# DVD.net
KiCad netlist of a schematic drawn in Altium Designer
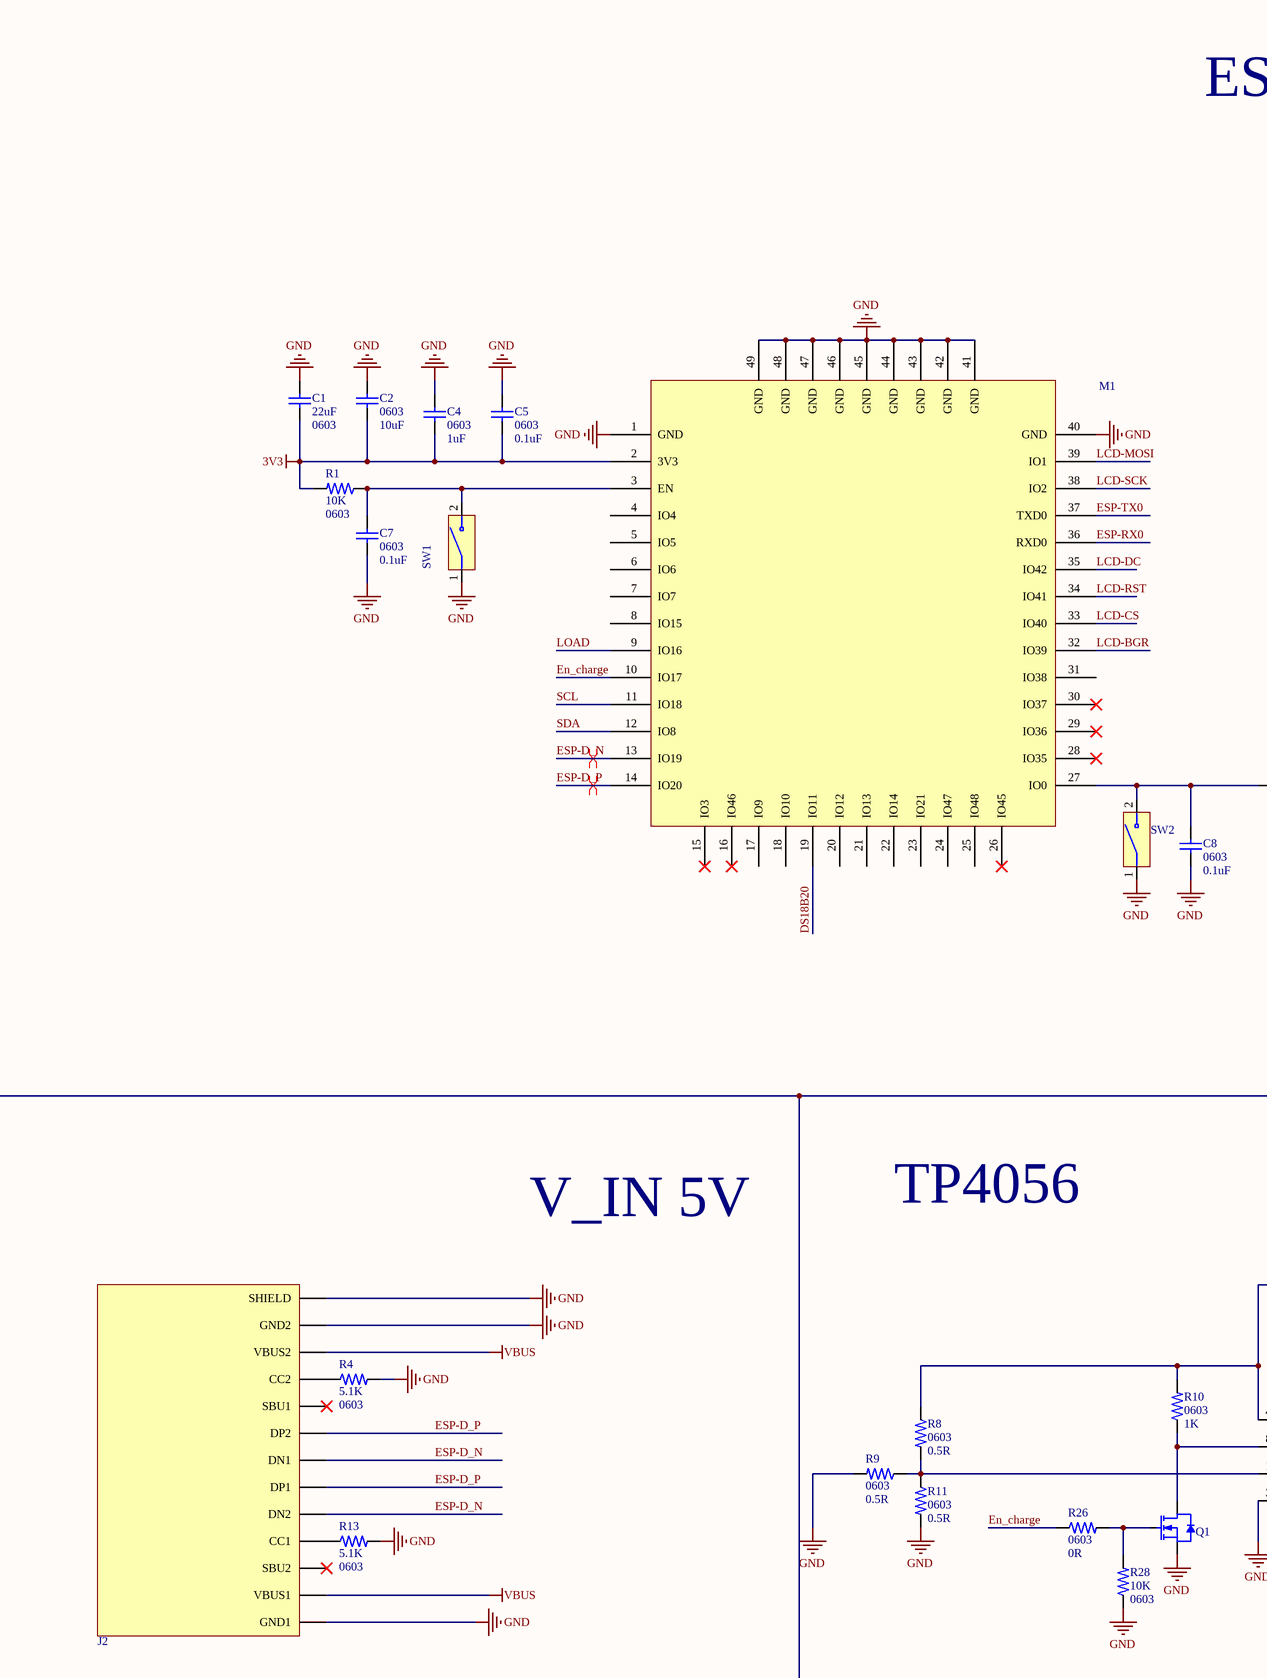
[diagram p0: DVD.SchDoc, top left]
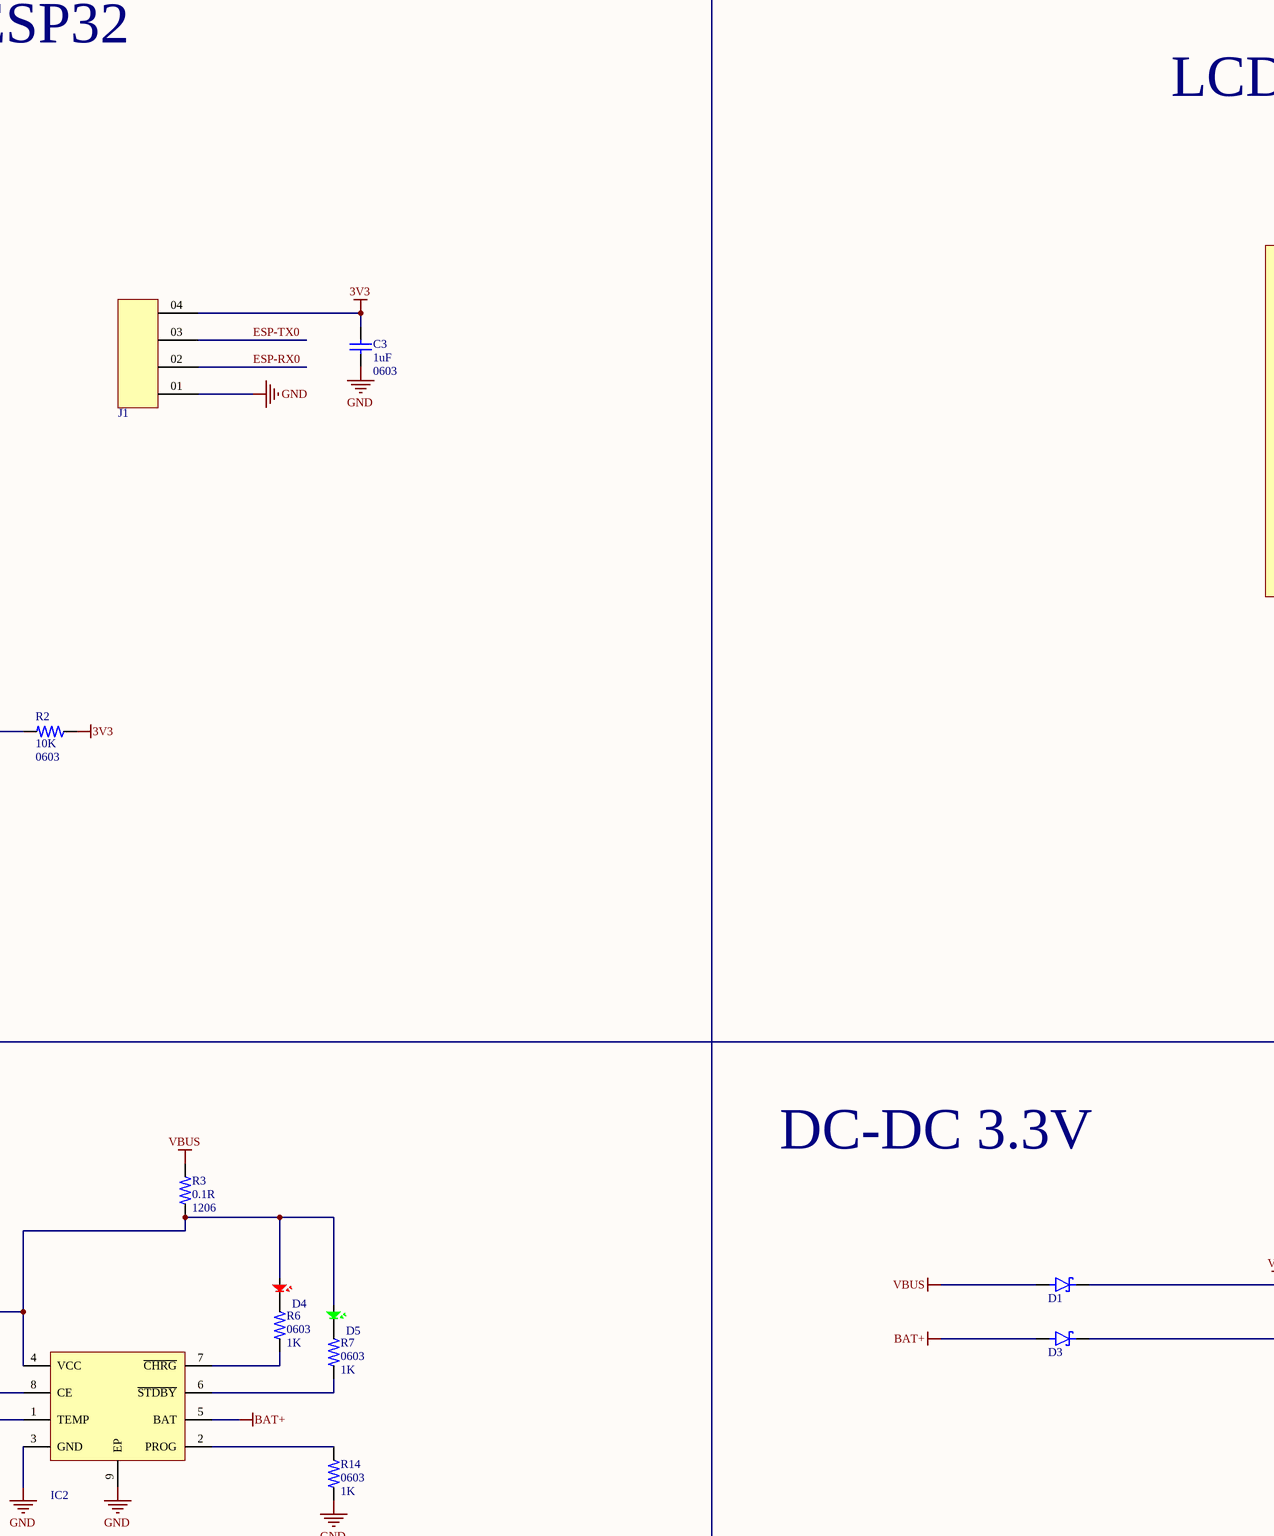
[diagram p1: DVD.SchDoc, top middle]
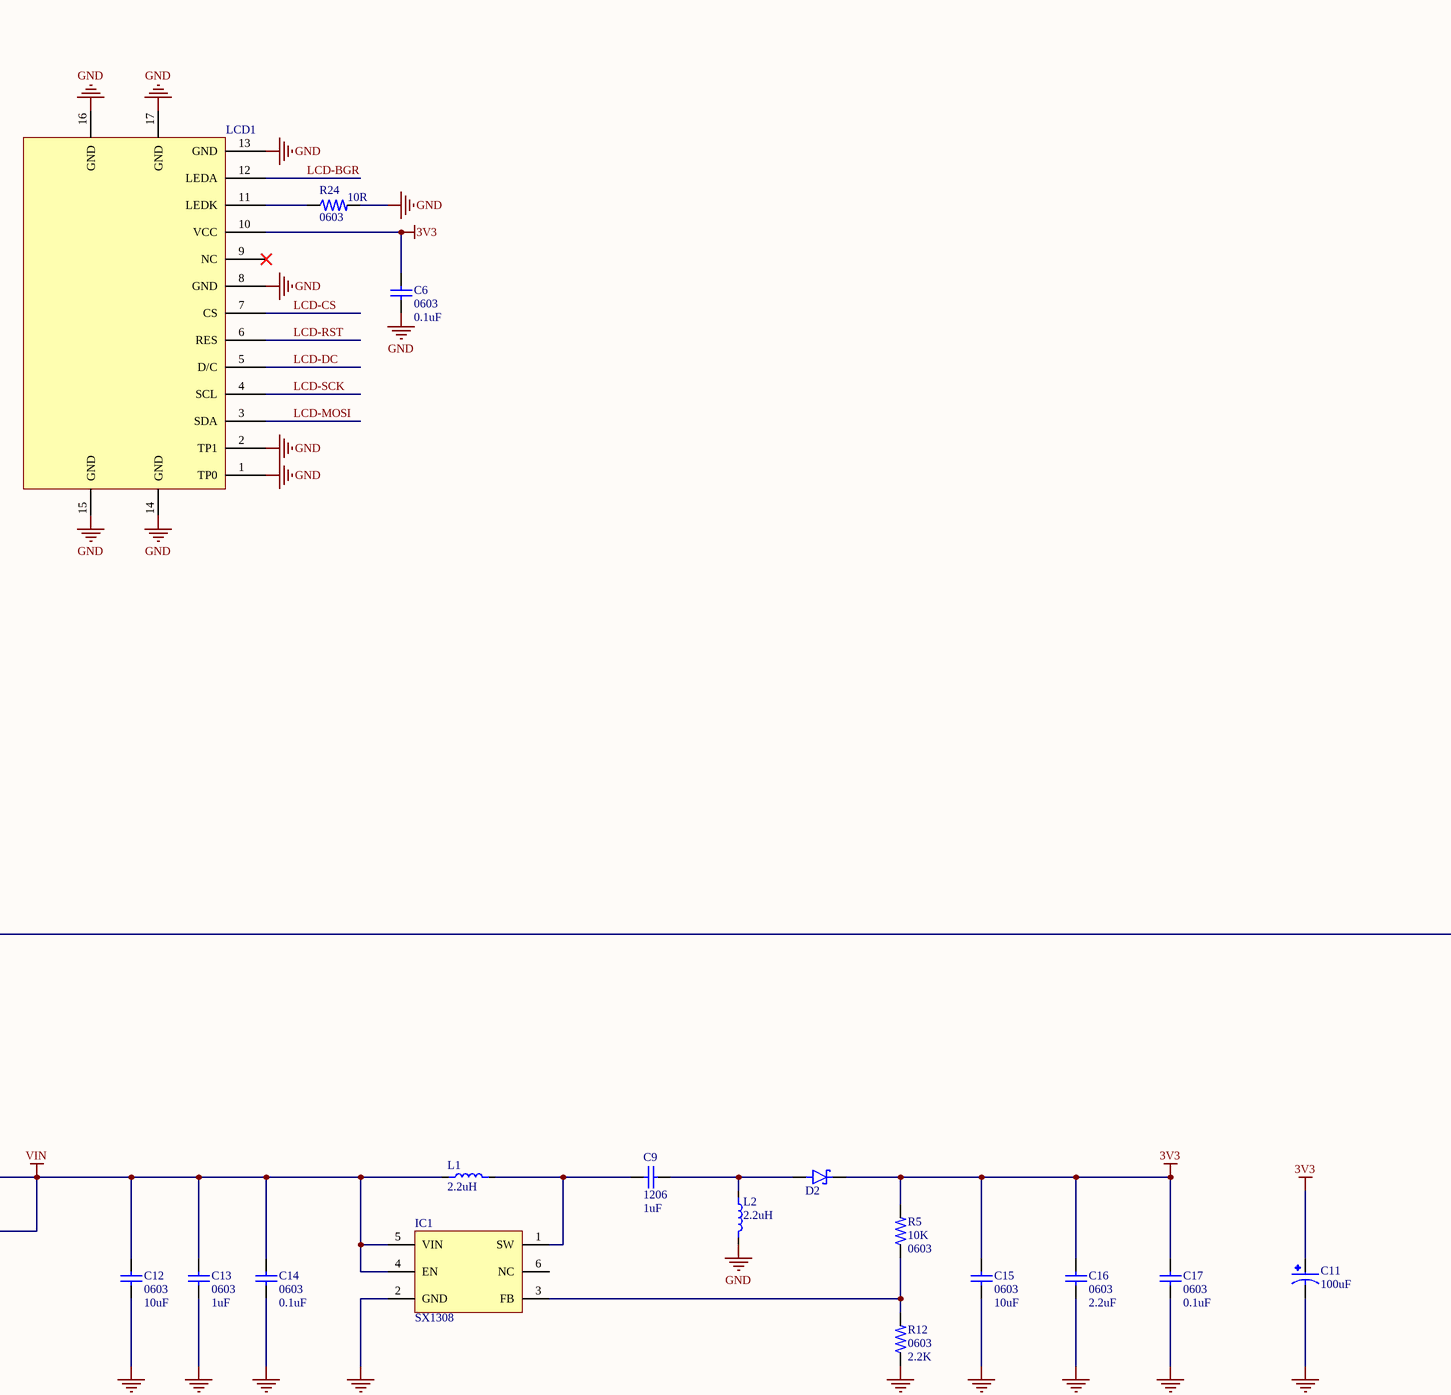
[diagram p2: DVD.SchDoc, top right]
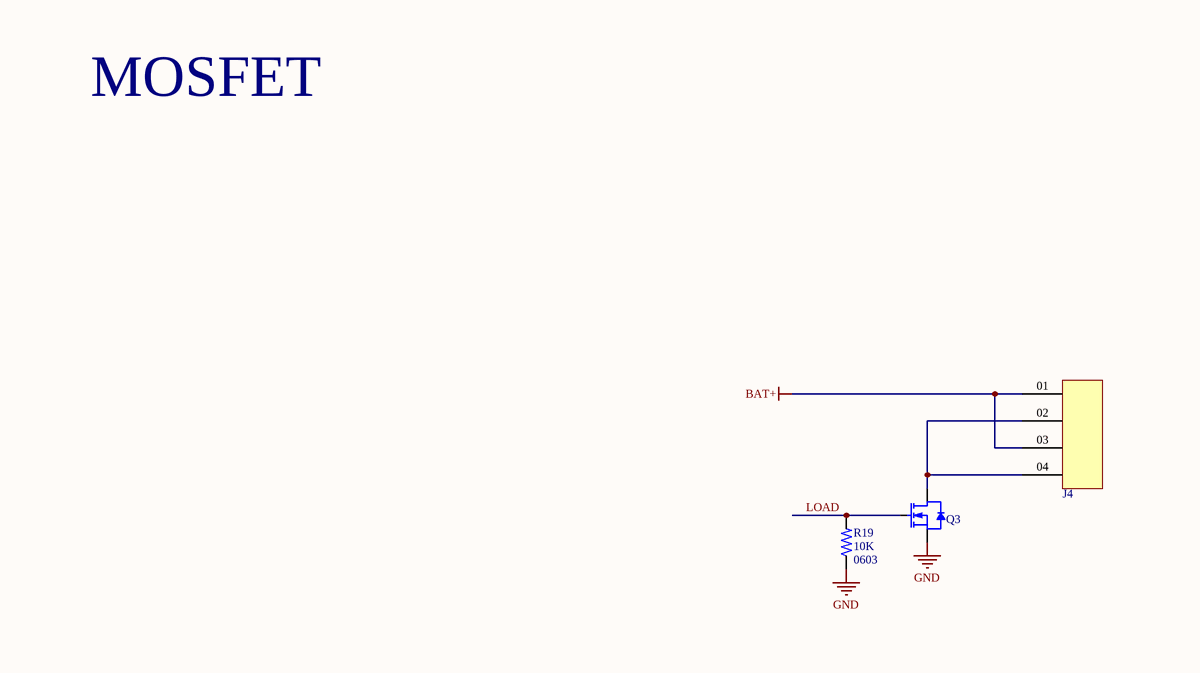
[diagram p3: DVD.SchDoc, bottom left]
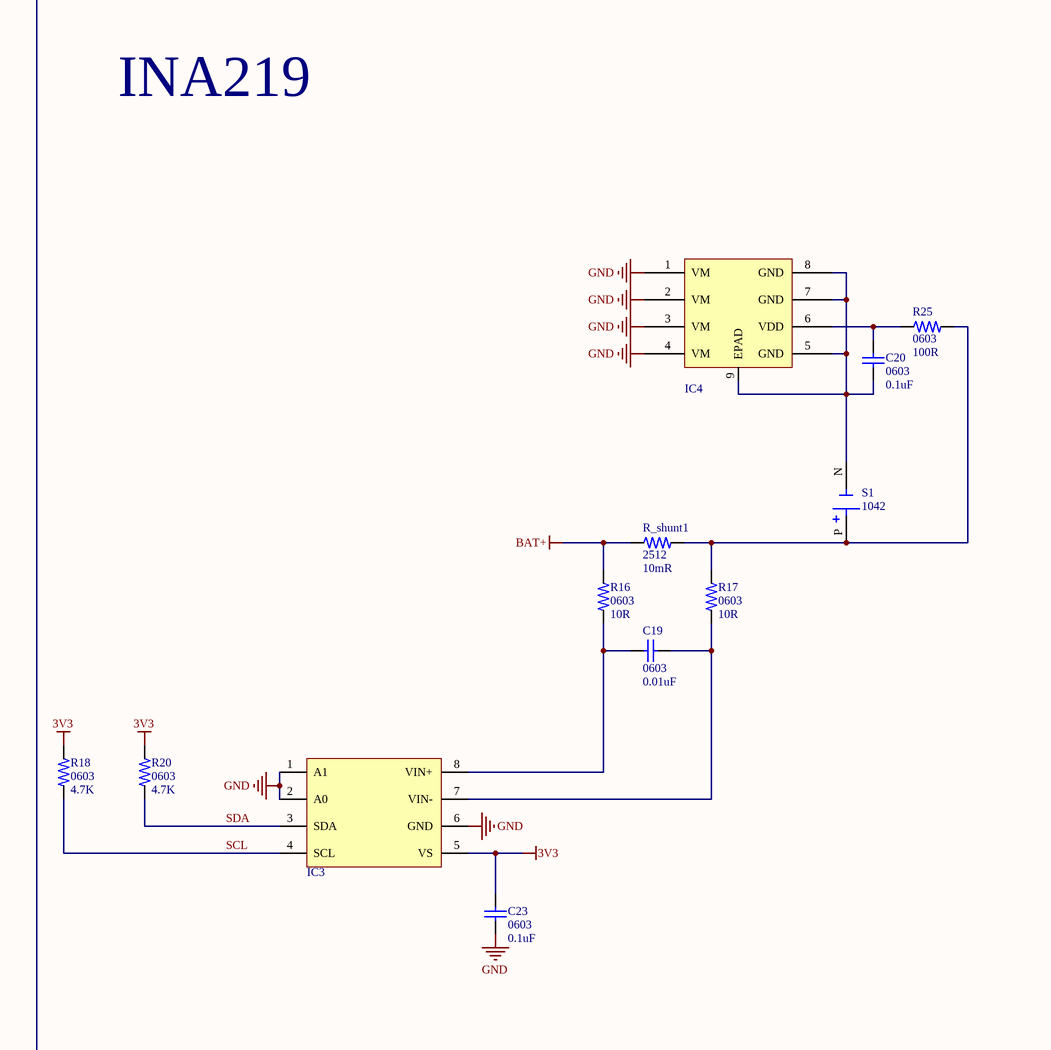
[diagram p4: DVD.SchDoc, bottom middle]
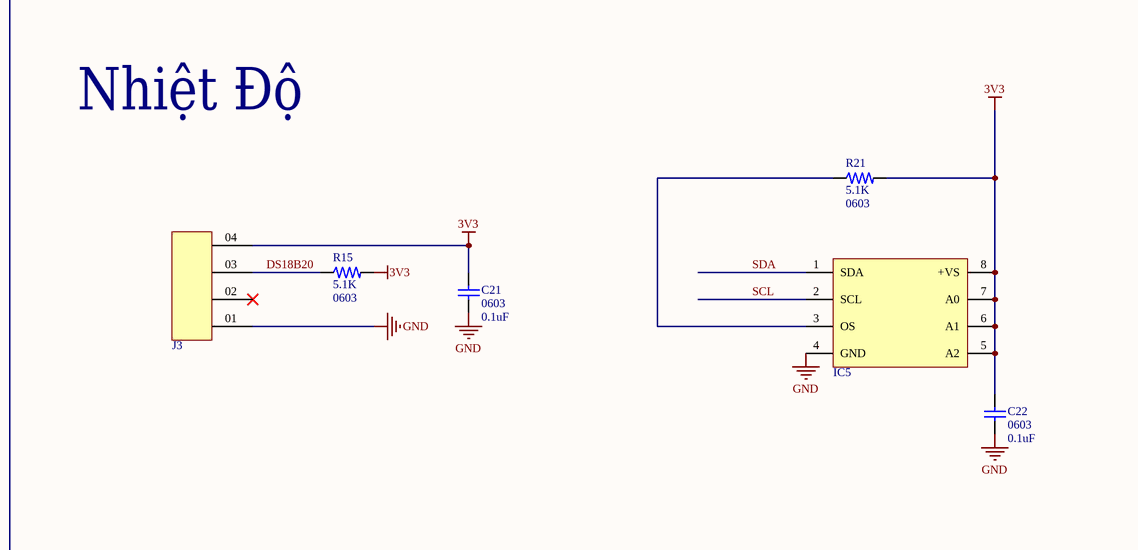
[diagram p5: DVD.SchDoc, bottom right]

(export (version "E")
  (design (tool "Eeschema 10.0.6"))
  (components
    (comp (ref "C1")
      (value "22uF")
      (footprint "SMD-CAP-0603-YAGEO")
      (description "Multilayer Ceramic Capacitor, 22 uF, 10 V, ï¿½ 20%, X5R, 0603 [1608 Metric]")
      (fields
        (field (name "MANUFACTURER") "Yageo")
        (field (name "MANUFACTURER PART NUMBER") "CC0603MRX5R6BB226")
        (field (name "PACKAGE") "0603")
        (field (name "DESIGNER") "TVBac")
      )
      (libsource (lib "Capacitors") (part "CAP; 22uF; 25V; SMD; CC0603MRX5R6BB226"))
    )
    (comp (ref "C2")
      (value "10uF")
      (footprint "SMD-CAP-0603-YAGEO")
      (description "Multilayer Ceramic Capacitor, 10 uF, 25 V, ï¿½ 20%, X5R, 0603 [1608 Metric]")
      (fields
        (field (name "MANUFACTURER") "Yageo")
        (field (name "MANUFACTURER PART NUMBER") "CC0603MRX5R8BB106")
        (field (name "PACKAGE") "0603")
        (field (name "DESIGNER") "TVBac")
      )
      (libsource (lib "Capacitors") (part "CAP; 10uF; 25V; SMD; 0603; CC0603MRX5R8BB106"))
    )
    (comp (ref "C3")
      (value "1uF")
      (footprint "SMD-CAP-0603-YAGEO")
      (description "0603 1 uF 16 V ±10 % Tolerance X7R SMT Multilayer Ceramic Capacitor")
      (fields
        (field (name "MANUFACTURER") "Yageo")
        (field (name "MANUFACTURER PART NUMBER") "CC0603KRX7R7BB105")
        (field (name "PACKAGE") "0603")
        (field (name "DESIGNER") "TVBac")
      )
      (libsource (lib "Capacitors") (part "CAP; 1uF; 16V; 0603; SMD; CC0603KRX7R7BB105"))
    )
    (comp (ref "C4")
      (value "1uF")
      (footprint "SMD-CAP-0603-YAGEO")
      (description "Surface Mount Ceramic Multilayer Capacitor 1uF -20% to 80% Y5V 10V 0603 Paper T/R")
      (fields
        (field (name "MANUFACTURER") "Yageo")
        (field (name "MANUFACTURER PART NUMBER") "CC0603ZRY5V6BB105")
        (field (name "PACKAGE") "0603")
        (field (name "DESIGNER") "TVBac")
      )
      (libsource (lib "Capacitors") (part "CAP; 1uF; 10V; 0603; SMD; CC0603ZRY5V6BB105"))
    )
    (comp (ref "C5")
      (value "0.1uF")
      (footprint "SMD-CAP-0603-YAGEO")
      (description "0603 0.1 uF 16 V ±10 % Tolerance X7R SMT Multilayer Ceramic Capacitor")
      (fields
        (field (name "MANUFACTURER") "Yageo")
        (field (name "MANUFACTURER PART NUMBER") "CC0603KRX7R7BB104")
        (field (name "PACKAGE") "0603")
        (field (name "DESIGNER") "TVBac")
      )
      (libsource (lib "Capacitors") (part "CAP; 0.1uF; 16V; 0603; SMD; CC0603KRX7R7BB104"))
    )
    (comp (ref "C6")
      (value "0.1uF")
      (footprint "SMD-CAP-0603-YAGEO")
      (description "0603 0.1 uF 16 V ±10 % Tolerance X7R SMT Multilayer Ceramic Capacitor")
      (fields
        (field (name "MANUFACTURER") "Yageo")
        (field (name "MANUFACTURER PART NUMBER") "CC0603KRX7R7BB104")
        (field (name "PACKAGE") "0603")
        (field (name "DESIGNER") "TVBac")
      )
      (libsource (lib "Capacitors") (part "CAP; 0.1uF; 16V; 0603; SMD; CC0603KRX7R7BB104"))
    )
    (comp (ref "C7")
      (value "0.1uF")
      (footprint "SMD-CAP-0603-YAGEO")
      (description "Multilayer Ceramic Capacitors MLCC - SMD/SMT 100V 0.1uF X7R 0603 10%")
      (fields
        (field (name "MANUFACTURER") "Yageo")
        (field (name "MANUFACTURER PART NUMBER") "CC0603KRX7R0BB104")
        (field (name "PACKAGE") "0603")
        (field (name "DESIGNER") "TVBac")
      )
      (libsource (lib "Capacitors") (part "CAP; 0.1uF; 100V; 0603; SMD; CC0603KRX7R0BB104"))
    )
    (comp (ref "C8")
      (value "0.1uF")
      (footprint "SMD-CAP-0603-YAGEO")
      (description "Multilayer Ceramic Capacitors MLCC - SMD/SMT 100V 0.1uF X7R 0603 10%")
      (fields
        (field (name "MANUFACTURER") "Yageo")
        (field (name "MANUFACTURER PART NUMBER") "CC0603KRX7R0BB104")
        (field (name "PACKAGE") "0603")
        (field (name "DESIGNER") "TVBac")
      )
      (libsource (lib "Capacitors") (part "CAP; 0.1uF; 100V; 0603; SMD; CC0603KRX7R0BB104"))
    )
    (comp (ref "C9")
      (value "1uF")
      (footprint "SMD-CAP-1206-KEMET")
      (description "Multilayer Ceramic Capacitor, 1 uF, 100 V, ± 10%, X7R, 1206 [3216 Metric]")
      (fields
        (field (name "MANUFACTURER") "KEMET")
        (field (name "MANUFACTURER PART NUMBER") "C1206C105K1RACTU")
        (field (name "PACKAGE") "1206")
        (field (name "DESIGNER") "TVBac")
      )
      (libsource (lib "Capacitors") (part "CAP; 1uF; 100V; 1206; C1206C105K1RACTU"))
    )
    (comp (ref "C11")
      (value "100uF")
      (footprint "SMD-DxLxW-6.3x6.6x6.6-PEC")
      (description "Cap Aluminum 100uF 25V 20% (6.3 X 7.7mm) SMD 0.03 Ohm 2000mA 5000h 105 C Embossed T/R")
      (fields
        (field (name "MANUFACTURER") "Panasonic")
        (field (name "MANUFACTURER PART NUMBER") "EEH-ZA1E101XP")
        (field (name "DESIGNER") "TVBac")
      )
      (libsource (lib "Capacitors") (part "CAP; 100uF; 25V; SMD; EEH-ZA1E101XP"))
    )
    (comp (ref "C12")
      (value "10uF")
      (footprint "SMD-CAP-0603-YAGEO")
      (description "Multilayer Ceramic Capacitor, 10 uF, 25 V, ï¿½ 20%, X5R, 0603 [1608 Metric]")
      (fields
        (field (name "MANUFACTURER") "Yageo")
        (field (name "MANUFACTURER PART NUMBER") "CC0603MRX5R8BB106")
        (field (name "PACKAGE") "0603")
        (field (name "DESIGNER") "TVBac")
      )
      (libsource (lib "Capacitors") (part "CAP; 10uF; 25V; SMD; 0603; CC0603MRX5R8BB106"))
    )
    (comp (ref "C13")
      (value "1uF")
      (footprint "SMD-CAP-0603-YAGEO")
      (description "Surface Mount Ceramic Multilayer Capacitor 1uF -20% to 80% Y5V 10V 0603 Paper T/R")
      (fields
        (field (name "MANUFACTURER") "Yageo")
        (field (name "MANUFACTURER PART NUMBER") "CC0603ZRY5V6BB105")
        (field (name "PACKAGE") "0603")
        (field (name "DESIGNER") "TVBac")
      )
      (libsource (lib "Capacitors") (part "CAP; 1uF; 10V; 0603; SMD; CC0603ZRY5V6BB105"))
    )
    (comp (ref "C14")
      (value "0.1uF")
      (footprint "SMD-CAP-0603-YAGEO")
      (description "0603 0.1 uF 16 V ±10 % Tolerance X7R SMT Multilayer Ceramic Capacitor")
      (fields
        (field (name "MANUFACTURER") "Yageo")
        (field (name "MANUFACTURER PART NUMBER") "CC0603KRX7R7BB104")
        (field (name "PACKAGE") "0603")
        (field (name "DESIGNER") "TVBac")
      )
      (libsource (lib "Capacitors") (part "CAP; 0.1uF; 16V; 0603; SMD; CC0603KRX7R7BB104"))
    )
    (comp (ref "C15")
      (value "10uF")
      (footprint "SMD-CAP-0603-YAGEO")
      (description "Multilayer Ceramic Capacitor, 10 uF, 25 V, ï¿½ 20%, X5R, 0603 [1608 Metric]")
      (fields
        (field (name "MANUFACTURER") "Yageo")
        (field (name "MANUFACTURER PART NUMBER") "CC0603MRX5R8BB106")
        (field (name "PACKAGE") "0603")
        (field (name "DESIGNER") "TVBac")
      )
      (libsource (lib "Capacitors") (part "CAP; 10uF; 25V; SMD; 0603; CC0603MRX5R8BB106"))
    )
    (comp (ref "C16")
      (value "2.2uF")
      (footprint "SMD-CAP-0603-YAGEO")
      (description "0603 2.2 uF 25 V ±10% Tolerance X5R SMT Multilayer Ceramic Capacitor")
      (fields
        (field (name "MANUFACTURER") "Yageo")
        (field (name "MANUFACTURER PART NUMBER") "CC0603KRX5R8BB225")
        (field (name "PACKAGE") "0603")
        (field (name "DESIGNER") "TVBac")
      )
      (libsource (lib "Capacitors") (part "CAP; 2.2uF; 25V; SMD; 0603; CC0603KRX5R8BB225"))
    )
    (comp (ref "C17")
      (value "0.1uF")
      (footprint "SMD-CAP-0603-YAGEO")
      (description "Multilayer Ceramic Capacitors MLCC - SMD/SMT 100V 0.1uF X7R 0603 10%")
      (fields
        (field (name "MANUFACTURER") "Yageo")
        (field (name "MANUFACTURER PART NUMBER") "CC0603KRX7R0BB104")
        (field (name "PACKAGE") "0603")
        (field (name "DESIGNER") "TVBac")
      )
      (libsource (lib "Capacitors") (part "CAP; 0.1uF; 100V; 0603; SMD; CC0603KRX7R0BB104"))
    )
    (comp (ref "C19")
      (value "0.01uF")
      (footprint "SMD-CAP-0603-YAGEO")
      (description "Multilayer Ceramic Capacitor, 0.1 uF, 10 V, ± 10%, X7R, 0603 [1608 Metric]")
      (fields
        (field (name "MANUFACTURER") "Yageo")
        (field (name "MANUFACTURER PART NUMBER") "CC0603KRX7R6BB104")
        (field (name "PACKAGE") "0603")
        (field (name "DESIGNER") "TVBac")
      )
      (libsource (lib "Capacitors") (part "CAP; 0.1uF; 10V; 0603; SMD; CC0603KRX7R6BB104"))
    )
    (comp (ref "C20")
      (value "0.1uF")
      (footprint "SMD-CAP-0603-YAGEO")
      (description "0603 0.1 uF 16 V ±10 % Tolerance X7R SMT Multilayer Ceramic Capacitor")
      (fields
        (field (name "MANUFACTURER") "Yageo")
        (field (name "MANUFACTURER PART NUMBER") "CC0603KRX7R7BB104")
        (field (name "PACKAGE") "0603")
        (field (name "DESIGNER") "TVBac")
      )
      (libsource (lib "Capacitors") (part "CAP; 0.1uF; 16V; 0603; SMD; CC0603KRX7R7BB104"))
    )
    (comp (ref "C21")
      (value "0.1uF")
      (footprint "SMD-CAP-0603-YAGEO")
      (description "0603 0.1 uF 16 V ±10 % Tolerance X7R SMT Multilayer Ceramic Capacitor")
      (fields
        (field (name "MANUFACTURER") "Yageo")
        (field (name "MANUFACTURER PART NUMBER") "CC0603KRX7R7BB104")
        (field (name "PACKAGE") "0603")
        (field (name "DESIGNER") "TVBac")
      )
      (libsource (lib "Capacitors") (part "CAP; 0.1uF; 16V; 0603; SMD; CC0603KRX7R7BB104"))
    )
    (comp (ref "C22")
      (value "0.1uF")
      (footprint "SMD-CAP-0603-YAGEO")
      (description "0603 0.1 uF 16 V ±10 % Tolerance X7R SMT Multilayer Ceramic Capacitor")
      (fields
        (field (name "MANUFACTURER") "Yageo")
        (field (name "MANUFACTURER PART NUMBER") "CC0603KRX7R7BB104")
        (field (name "PACKAGE") "0603")
        (field (name "DESIGNER") "TVBac")
      )
      (libsource (lib "Capacitors") (part "CAP; 0.1uF; 16V; 0603; SMD; CC0603KRX7R7BB104"))
    )
    (comp (ref "C23")
      (value "0.1uF")
      (footprint "SMD-CAP-0603-YAGEO")
      (description "0603 0.1 uF 16 V ±10 % Tolerance X7R SMT Multilayer Ceramic Capacitor")
      (fields
        (field (name "MANUFACTURER") "Yageo")
        (field (name "MANUFACTURER PART NUMBER") "CC0603KRX7R7BB104")
        (field (name "PACKAGE") "0603")
        (field (name "DESIGNER") "TVBac")
      )
      (libsource (lib "Capacitors") (part "CAP; 0.1uF; 16V; 0603; SMD; CC0603KRX7R7BB104"))
    )
    (comp (ref "D1")
      (value "Diode 40 V 3A Surface Mount DO-214AC (SMA)")
      (footprint "SMD-DO-214AC-214-CT")
      (description "Diode Schottky Si 40V 3A 2-Pin SMA T/R")
      (fields
        (field (name "MANUFACTURER") "Comchip")
        (field (name "MANUFACTURER PART NUMBER") "SS34-HF")
        (field (name "DESIGNER") "TVBac")
      )
      (libsource (lib "Diode") (part "DIODE; SMD; SCHOTTKY; SS34-HF"))
    )
    (comp (ref "D2")
      (value "Diode 40 V 3A Surface Mount DO-214AC (SMA)")
      (footprint "SMD-DO-214AC-214-CT")
      (description "Diode Schottky Si 40V 3A 2-Pin SMA T/R")
      (fields
        (field (name "MANUFACTURER") "Comchip")
        (field (name "MANUFACTURER PART NUMBER") "SS34-HF")
        (field (name "DESIGNER") "TVBac")
      )
      (libsource (lib "Diode") (part "DIODE; SMD; SCHOTTKY; SS34-HF"))
    )
    (comp (ref "D3")
      (value "Diode 40 V 3A Surface Mount DO-214AC (SMA)")
      (footprint "SMD-DO-214AC-214-CT")
      (description "Diode Schottky Si 40V 3A 2-Pin SMA T/R")
      (fields
        (field (name "MANUFACTURER") "Comchip")
        (field (name "MANUFACTURER PART NUMBER") "SS34-HF")
        (field (name "DESIGNER") "TVBac")
      )
      (libsource (lib "Diode") (part "DIODE; SMD; SCHOTTKY; SS34-HF"))
    )
    (comp (ref "D4")
      (value "0603 RED")
      (footprint "LED0603_RED")
      (fields
        (field (name "MANUFACTURER") "XINGLIGHT")
        (field (name "MANUFACTURE PART NUMBER") "XL-1608SURC-06")
      )
      (libsource (lib "LED") (part "L0603_RED"))
    )
    (comp (ref "D5")
      (value "0603 GREEN")
      (footprint "LED0603_GREEN")
      (fields
        (field (name "MANUFACTURER") "Amicc")
        (field (name "MANUFACTURE PART NUMBER") "A-SP192DGHC-C01-4T")
      )
      (libsource (lib "LED") (part "L0603_GREEN"))
    )
    (comp (ref "IC1")
      (value "SX1308")
      (footprint "SOT23-6-SX1308")
      (description "Boost type Adjustable 28V 2A 2V~24V SOT-23-6 DC-DC Converters ROHS")
      (fields (field (name "MANUFACTURER") "SX(Shenzhen Suosemi Tech)") (field (name "LCSC PART") "C78162"))
      (libsource (lib "IC") (part "SX1308"))
    )
    (comp (ref "IC2") (value "TP4056") (footprint "SOIC-8-TP4056") (libsource (lib "IC") (part "TP4056")))
    (comp (ref "IC3")
      (value "Current Monitor Regulator High-Side 10mA 8-SOIC")
      (footprint "SOIC-8-TI")
      (description "26-V 12-bit I2C output digital power monitor 8-SOIC -40 to 125")
      (fields
        (field (name "MANUFACTURER") "Texas Instruments")
        (field (name "MANUFACTURER PART NUMBER") "INA219AIDR")
      )
      (libsource (lib "IC") (part "INA219AIDR"))
    )
    (comp (ref "IC4") (value "XB8089D") (footprint "SOIC-8-XB8089D") (libsource (lib "IC") (part "XB8089D")))
    (comp (ref "IC5")
      (value "Temperature Sensor Digital, Local -55°C ~ 125°C 9 b 8-SOIC")
      (footprint "SOIC-8-ADI")
      (description "Serial Switch/Digital Sensor, 9 Bit(s), 3Cel, CMOS, Rectangular, 8 Pin, Surface Mount")
      (fields
        (field (name "MANUFACTURER") "Analog Devices")
        (field (name "MANUFACTURER PART NUMBER") "LM75BIM-5+")
      )
      (libsource (lib "IC") (part "LM75BIM-5+"))
    )
    (comp (ref "J1")
      (value "Connector Header Through Hole 4 position 0.100\" (2.54mm)")
      (footprint "HEADER-2.54-4 - U3D")
      (description "Conn Unshrouded Header HDR 4 POS 2.54mm Solder ST Thru-Hole Automotive Bulk")
      (fields
        (field (name "MANUFACTURER") "Samtec")
        (field (name "MANUFACTURER PART NUMBER") "TSW-104-14-L-S")
        (field (name "DESIGNER") "TVBac")
      )
      (libsource (lib "Socket") (part "HEADER; 4PIN; 2.54; VER; TSW-104-14-L-S"))
    )
    (comp (ref "J2")
      (value "USB-C (USB TYPE-C) USB 2.0 Receptacle Connector 24 (16+8 Dummy) Position Surface Mount, Right Angle; Through Hole")
      (footprint "TYPE-C-HOR-RECEPTACLE-24PIN-MOLEX")
      (description "USB Connector, 16 Contact(s), Female, Right Angle, Surface Mount Terminal, Locking, Receptacle")
      (fields
        (field (name "MANUFACTURER") "Molex")
        (field (name "MANUFACTURER PART NUMBER") "217179-0001")
        (field (name "DESIGNER") "TVBac")
      )
      (libsource (lib "Socket") (part "Type-C; USB; HOR; RECEPTACLE;  24PIN; 217179-0001"))
    )
    (comp (ref "J3")
      (value "Connector Header Through Hole 4 position 0.100\" (2.54mm)")
      (footprint "HEADER-2.54-4 - U3D")
      (description "Conn Unshrouded Header HDR 4 POS 2.54mm Solder ST Thru-Hole Automotive Bulk")
      (fields
        (field (name "MANUFACTURER") "Samtec")
        (field (name "MANUFACTURER PART NUMBER") "TSW-104-14-L-S")
        (field (name "DESIGNER") "TVBac")
      )
      (libsource (lib "Socket") (part "HEADER; 4PIN; 2.54; VER; TSW-104-14-L-S"))
    )
    (comp (ref "J4")
      (value "Connector Header Through Hole 4 position 0.100\" (2.54mm)")
      (footprint "HEADER-2.54-4 - U3D")
      (description "Conn Unshrouded Header HDR 4 POS 2.54mm Solder ST Thru-Hole Automotive Bulk")
      (fields
        (field (name "MANUFACTURER") "Samtec")
        (field (name "MANUFACTURER PART NUMBER") "TSW-104-14-L-S")
        (field (name "DESIGNER") "TVBac")
      )
      (libsource (lib "") (part "HEADER; 4PIN; 2.54; VER; TSW-104-14-L-S_1"))
    )
    (comp (ref "L1")
      (value "2.2uH")
      (footprint "SMD-HxLxW-3.0x5.5x5.0-PEC")
      (description "Ind Power Shielded Wirewound 2.2uH 20% 100KHz Metal 6.3A (5.5 X 5 X 3mm) Emboss T/R")
      (fields
        (field (name "MANUFACTURER") "Panasonic")
        (field (name "MANUFACTURER PART NUMBER") "ETQ-P3M2R2KVP")
        (field (name "DESIGNER") "TVBac")
      )
      (libsource (lib "Inductors") (part "IND; 2.2uH; SMD; 6.3A; ETQ-P3M2R2KVP"))
    )
    (comp (ref "L2")
      (value "2.2uH")
      (footprint "SMD-HxLxW-3.0x5.5x5.0-PEC")
      (description "Ind Power Shielded Wirewound 2.2uH 20% 100KHz Metal 6.3A (5.5 X 5 X 3mm) Emboss T/R")
      (fields
        (field (name "MANUFACTURER") "Panasonic")
        (field (name "MANUFACTURER PART NUMBER") "ETQ-P3M2R2KVP")
        (field (name "DESIGNER") "TVBac")
      )
      (libsource (lib "Inductors") (part "IND; 2.2uH; SMD; 6.3A; ETQ-P3M2R2KVP"))
    )
    (comp (ref "LCD1")
      (value "LCD ST7789")
      (footprint "ST7735S-80x160-0.96INCH")
      (libsource (lib "LCD") (part "LCD; ST7735; 0.96Inch;"))
    )
    (comp (ref "M1")
      (value "Bluetooth, WiFi 802.11b/g/n, Bluetooth v4.2 +EDR Transceiver Module 2.4GHz ~ 2.5GHz PCB Trace Surface Mount")
      (footprint "MODULE-ESP32-S3-WROOM-1-N16R8")
      (description "SMD mod, ESP32-S3R8 with 3.3V, 8MB Octal PSRAM die insid, 6MBQuad SPI flash, pcb ant")
      (fields
        (field (name "MANUFACTURER") "Espressif Systems")
        (field (name "MANUFACTURER PART NUMBER") "ESP32-S3-WROOM-1-N16R8")
        (field (name "DESIGNER") "TVBac")
      )
      (libsource (lib "Modules") (part "ESP32-S3-WROOM-1-N16R8; SMD;"))
    )
    (comp (ref "Q1")
      (value "N-Channel 30 V 5.7A (Ta) 1.4W (Ta) Surface Mount SOT-23-3")
      (footprint "SOT23-3-AOEI")
      (description "Trans MOSFET N-CH 30V 5.7A 3-Pin SOT-23")
      (fields
        (field (name "MANUFACTURER") "Alpha & Omega Semiconductor")
        (field (name "MANUFACTURER PART NUMBER") "AO3400A")
      )
      (libsource (lib "MOSFET") (part "SMD; AO3400A; MOSFET; N-CH;"))
    )
    (comp (ref "Q3")
      (value "N-Channel 60 V 7A (Ta), 37A (Tc) 2.1W (Ta), 60W (Tc) Surface Mount TO-252 (DPAK)")
      (footprint "TO252")
      (description "Trans MOSFET N-CH 60V 37A 3-Pin(2+Tab) DPAK")
      (fields
        (field (name "MANUFACTURER") "Alpha & Omega Semiconductor")
        (field (name "MANUFACTURER PART NUMBER") "AOD442")
        (field (name "DESIGNER") "TVBac")
      )
      (libsource (lib "MOSFET") (part "SMD; AOD442; MOSFET; N-CH;"))
    )
    (comp (ref "R1")
      (value "10K")
      (footprint "SMD-RES-0603-YAGEO")
      (description "SMD Chip Resistor, 10 Kohm, ½ 1%, 100 Mw, 0603 [1608 Metric], Thick Film, General Purpose")
      (fields
        (field (name "MANUFACTURER") "Yageo")
        (field (name "MANUFACTURER PART NUMBER") "RC0603FR-0710KL")
        (field (name "PACKAGE") "0603")
      )
      (libsource (lib "Resistors") (part "RES; 10K; 0603; SMD; RC0603FR-0710KL"))
    )
    (comp (ref "R2")
      (value "10K")
      (footprint "SMD-RES-0603-YAGEO")
      (description "SMD Chip Resistor, 10 Kohm, ½ 1%, 100 Mw, 0603 [1608 Metric], Thick Film, General Purpose")
      (fields
        (field (name "MANUFACTURER") "Yageo")
        (field (name "MANUFACTURER PART NUMBER") "RC0603FR-0710KL")
        (field (name "PACKAGE") "0603")
      )
      (libsource (lib "Resistors") (part "RES; 10K; 0603; SMD; RC0603FR-0710KL"))
    )
    (comp (ref "R3")
      (value "0.1R")
      (footprint "SMD-RES-1206-YAGEO")
      (description "SMD Chip Resistor, 100 MOhm, ± 5%, 250 mW, 1206 [3216 Metric], Thick Film, Low Ohmic")
      (fields
        (field (name "MANUFACTURER") "Yageo")
        (field (name "MANUFACTURER PART NUMBER") "RL1206JR-070R1L")
        (field (name "PACKAGE") "1206")
      )
      (libsource (lib "Resistors") (part "RES; 0.1R; 1206; SMD; RL1206JR-070R1L"))
    )
    (comp (ref "R4")
      (value "5.1K")
      (footprint "SMD-RES-0603-SEI")
      (description "Res Thick Film 0603 5.1K Ohm 1% 0.1W(1/10W) ±100ppm/C Pad SMD T/R Automotive AEC-Q200")
      (fields
        (field (name "MANUFACTURER") "Stackpole Electronics")
        (field (name "MANUFACTURER PART NUMBER") "RMCF0603FT5K10")
        (field (name "PACKAGE") "0603")
      )
      (libsource (lib "Resistors") (part "RES; 5.1K; 0603; SMD; RMCF0603FT5K10"))
    )
    (comp (ref "R5")
      (value "10K")
      (footprint "SMD-RES-0603-YAGEO")
      (description "SMD Chip Resistor, 10 Kohm, ½ 1%, 100 Mw, 0603 [1608 Metric], Thick Film, General Purpose")
      (fields
        (field (name "MANUFACTURER") "Yageo")
        (field (name "MANUFACTURER PART NUMBER") "RC0603FR-0710KL")
        (field (name "PACKAGE") "0603")
      )
      (libsource (lib "Resistors") (part "RES; 10K; 0603; SMD; RC0603FR-0710KL"))
    )
    (comp (ref "R6")
      (value "1K")
      (footprint "SMD-RES-0603-SEI")
      (description "SMD Chip Resistor, 1 kOhm, ± 1%, 250 mW, 0603 [1608 Metric], Thick Film, Anti-Surge")
      (fields
        (field (name "MANUFACTURER") "Rohm")
        (field (name "MANUFACTURER PART NUMBER") "ESR03EZPF1001")
        (field (name "PACKAGE") "0603")
        (field (name "DESIGNER") "TVBac")
      )
      (libsource (lib "Resistors") (part "RES; 1K; 0603; SMD; ESR03EZPF1001"))
    )
    (comp (ref "R7")
      (value "1K")
      (footprint "SMD-RES-0603-SEI")
      (description "SMD Chip Resistor, 1 kOhm, ± 1%, 250 mW, 0603 [1608 Metric], Thick Film, Anti-Surge")
      (fields
        (field (name "MANUFACTURER") "Rohm")
        (field (name "MANUFACTURER PART NUMBER") "ESR03EZPF1001")
        (field (name "PACKAGE") "0603")
        (field (name "DESIGNER") "TVBac")
      )
      (libsource (lib "Resistors") (part "RES; 1K; 0603; SMD; ESR03EZPF1001"))
    )
    (comp (ref "R8")
      (value "0.5R")
      (footprint "SMD-RES-0603-RS")
      (description "Res Thick Film 0603 0.51 Ohm 1% 0.2W(1/5W) 0ppm/C to 150ppm/C Pad SMD T/R Automotive AEC-Q200")
      (fields
        (field (name "MANUFACTURER") "Rohm")
        (field (name "MANUFACTURER PART NUMBER") "UCR03EVPFLR510")
        (field (name "PACKAGE") "0603")
        (field (name "DESIGNER") "TVBac")
      )
      (libsource (lib "Resistors") (part "RES; 0.5R; 0603; SMD; UCR03EVPFLR510"))
    )
    (comp (ref "R9")
      (value "0.5R")
      (footprint "SMD-RES-0603-RS")
      (description "Res Thick Film 0603 0.51 Ohm 1% 0.2W(1/5W) 0ppm/C to 150ppm/C Pad SMD T/R Automotive AEC-Q200")
      (fields
        (field (name "MANUFACTURER") "Rohm")
        (field (name "MANUFACTURER PART NUMBER") "UCR03EVPFLR510")
        (field (name "PACKAGE") "0603")
        (field (name "DESIGNER") "TVBac")
      )
      (libsource (lib "Resistors") (part "RES; 0.5R; 0603; SMD; UCR03EVPFLR510"))
    )
    (comp (ref "R10")
      (value "1K")
      (footprint "SMD-RES-0603-SEI")
      (description "SMD Chip Resistor, 1 kOhm, ± 1%, 250 mW, 0603 [1608 Metric], Thick Film, Anti-Surge")
      (fields
        (field (name "MANUFACTURER") "Rohm")
        (field (name "MANUFACTURER PART NUMBER") "ESR03EZPF1001")
        (field (name "PACKAGE") "0603")
        (field (name "DESIGNER") "TVBac")
      )
      (libsource (lib "Resistors") (part "RES; 1K; 0603; SMD; ESR03EZPF1001"))
    )
    (comp (ref "R11")
      (value "0.5R")
      (footprint "SMD-RES-0603-RS")
      (description "Res Thick Film 0603 0.51 Ohm 1% 0.2W(1/5W) 0ppm/C to 150ppm/C Pad SMD T/R Automotive AEC-Q200")
      (fields
        (field (name "MANUFACTURER") "Rohm")
        (field (name "MANUFACTURER PART NUMBER") "UCR03EVPFLR510")
        (field (name "PACKAGE") "0603")
        (field (name "DESIGNER") "TVBac")
      )
      (libsource (lib "Resistors") (part "RES; 0.5R; 0603; SMD; UCR03EVPFLR510"))
    )
    (comp (ref "R12")
      (value "2.2K")
      (footprint "SMD-RES-0603-SEI")
      (description "Res Thick Film 0603 2.2K Ohm 1% 0.1W(1/10W) ±100ppm/C Pad SMD Automotive T/R")
      (fields
        (field (name "MANUFACTURER") "Stackpole Electronics")
        (field (name "MANUFACTURER PART NUMBER") "RMCF0603FT2K20")
        (field (name "PACKAGE") "0603")
        (field (name "DESIGNER") "TVBac")
      )
      (libsource (lib "Resistors") (part "RES; 2.2K; SMD; 0603; RMCF0603FT2K20"))
    )
    (comp (ref "R13")
      (value "5.1K")
      (footprint "SMD-RES-0603-SEI")
      (description "Res Thick Film 0603 5.1K Ohm 1% 0.1W(1/10W) ±100ppm/C Pad SMD T/R Automotive AEC-Q200")
      (fields
        (field (name "MANUFACTURER") "Stackpole Electronics")
        (field (name "MANUFACTURER PART NUMBER") "RMCF0603FT5K10")
        (field (name "PACKAGE") "0603")
      )
      (libsource (lib "Resistors") (part "RES; 5.1K; 0603; SMD; RMCF0603FT5K10"))
    )
    (comp (ref "R14")
      (value "1K")
      (footprint "SMD-RES-0603-SEI")
      (description "SMD Chip Resistor, 1 kOhm, ± 1%, 250 mW, 0603 [1608 Metric], Thick Film, Anti-Surge")
      (fields
        (field (name "MANUFACTURER") "Rohm")
        (field (name "MANUFACTURER PART NUMBER") "ESR03EZPF1001")
        (field (name "PACKAGE") "0603")
        (field (name "DESIGNER") "TVBac")
      )
      (libsource (lib "Resistors") (part "RES; 1K; 0603; SMD; ESR03EZPF1001"))
    )
    (comp (ref "R15")
      (value "5.1K")
      (footprint "SMD-RES-0603-SEI")
      (description "Res Thick Film 0603 5.1K Ohm 1% 0.1W(1/10W) ±100ppm/C Pad SMD T/R Automotive AEC-Q200")
      (fields
        (field (name "MANUFACTURER") "Stackpole Electronics")
        (field (name "MANUFACTURER PART NUMBER") "RMCF0603FT5K10")
        (field (name "PACKAGE") "0603")
      )
      (libsource (lib "Resistors") (part "RES; 5.1K; 0603; SMD; RMCF0603FT5K10"))
    )
    (comp (ref "R16")
      (value "10R")
      (footprint "SMD-RES-0603-SE")
      (description "SMD Chip Resistor, 100 kOhm, ± 1%, 100 mW, 0603 [1608 Metric], Thick Film, General Purpose")
      (fields
        (field (name "MANUFACTURER") "Stackpole Electronics")
        (field (name "MANUFACTURER PART NUMBER") "RMCF0603FT10R0")
        (field (name "PACKAGE") "0603")
        (field (name "DESIGNER") "TVBac")
      )
      (libsource (lib "Resistors") (part "RES; 10R; SMD; 0603; RMCF0603FT10R0"))
    )
    (comp (ref "R17")
      (value "10R")
      (footprint "SMD-RES-0603-SE")
      (description "SMD Chip Resistor, 100 kOhm, ± 1%, 100 mW, 0603 [1608 Metric], Thick Film, General Purpose")
      (fields
        (field (name "MANUFACTURER") "Stackpole Electronics")
        (field (name "MANUFACTURER PART NUMBER") "RMCF0603FT10R0")
        (field (name "PACKAGE") "0603")
        (field (name "DESIGNER") "TVBac")
      )
      (libsource (lib "Resistors") (part "RES; 10R; SMD; 0603; RMCF0603FT10R0"))
    )
    (comp (ref "R18")
      (value "4.7K")
      (footprint "SMD-RES-0603-RS")
      (description "Res Anti-Sulfured Thick Film 0603 4.7k Ohm 1% 1/10W ±100ppm/°C Molded Paper T/R")
      (fields
        (field (name "MANUFACTURER") "Rohm")
        (field (name "MANUFACTURER PART NUMBER") "SFR03EZPF4701")
        (field (name "PACKAGE") "0603")
        (field (name "DESIGNER") "TVBac")
      )
      (libsource (lib "Resistors") (part "RES; 4.7K; 0603; SMD; SFR03EZPF4701"))
    )
    (comp (ref "R19")
      (value "10K")
      (footprint "SMD-RES-0603-YAGEO")
      (description "SMD Chip Resistor, 10 Kohm, ½ 1%, 100 Mw, 0603 [1608 Metric], Thick Film, General Purpose")
      (fields
        (field (name "MANUFACTURER") "Yageo")
        (field (name "MANUFACTURER PART NUMBER") "RC0603FR-0710KL")
        (field (name "PACKAGE") "0603")
      )
      (libsource (lib "Resistors") (part "RES; 10K; 0603; SMD; RC0603FR-0710KL"))
    )
    (comp (ref "R20")
      (value "4.7K")
      (footprint "SMD-RES-0603-RS")
      (description "Res Anti-Sulfured Thick Film 0603 4.7k Ohm 1% 1/10W ±100ppm/°C Molded Paper T/R")
      (fields
        (field (name "MANUFACTURER") "Rohm")
        (field (name "MANUFACTURER PART NUMBER") "SFR03EZPF4701")
        (field (name "PACKAGE") "0603")
        (field (name "DESIGNER") "TVBac")
      )
      (libsource (lib "Resistors") (part "RES; 4.7K; 0603; SMD; SFR03EZPF4701"))
    )
    (comp (ref "R21")
      (value "5.1K")
      (footprint "SMD-RES-0603-SEI")
      (description "Res Thick Film 0603 5.1K Ohm 1% 0.1W(1/10W) ±100ppm/C Pad SMD T/R Automotive AEC-Q200")
      (fields
        (field (name "MANUFACTURER") "Stackpole Electronics")
        (field (name "MANUFACTURER PART NUMBER") "RMCF0603FT5K10")
        (field (name "PACKAGE") "0603")
      )
      (libsource (lib "Resistors") (part "RES; 5.1K; 0603; SMD; RMCF0603FT5K10"))
    )
    (comp (ref "R24")
      (value "10R")
      (footprint "SMD-RES-0603-SE")
      (description "SMD Chip Resistor, 100 kOhm, ± 1%, 100 mW, 0603 [1608 Metric], Thick Film, General Purpose")
      (fields
        (field (name "MANUFACTURER") "Stackpole Electronics")
        (field (name "MANUFACTURER PART NUMBER") "RMCF0603FT10R0")
        (field (name "PACKAGE") "0603")
        (field (name "DESIGNER") "TVBac")
      )
      (libsource (lib "Resistors") (part "RES; 10R; SMD; 0603; RMCF0603FT10R0"))
    )
    (comp (ref "R25")
      (value "100R")
      (footprint "SMD-RES-0603-RS")
      (description "Res Thick Film 0603 100 Ohm 1% 0.1W(1/10W) ±100ppm/C Pad SMD T/R Automotive AEC-Q200")
      (fields
        (field (name "MANUFACTURER") "Rohm")
        (field (name "MANUFACTURER PART NUMBER") "KTR03EZPF1000")
        (field (name "PACKAGE") "0603")
        (field (name "DESIGNER") "TVBac")
      )
      (libsource (lib "Resistors") (part "RES; 100R; 0603; SMD; KTR03EZPF1000"))
    )
    (comp (ref "R26")
      (value "0R")
      (footprint "SMD-RES-0603-SEI")
      (description "Res Thick 0603 0 Ohm Jumper 1/10W 100Ppm/ C Smd Rohs Compliant: Yes")
      (fields
        (field (name "MANUFACTURER") "Stackpole Electronics")
        (field (name "MANUFACTURER PART NUMBER") "RMCF0603ZT0R00")
        (field (name "PACKAGE") "0603")
        (field (name "DESIGNER") "TVBac")
      )
      (libsource (lib "Resistors") (part "RES; 0R; 0603; SMD;  RMCF0603ZT0R00"))
    )
    (comp (ref "R28")
      (value "10K")
      (footprint "SMD-RES-0603-YAGEO")
      (description "SMD Chip Resistor, 10 Kohm, ½ 1%, 100 Mw, 0603 [1608 Metric], Thick Film, General Purpose")
      (fields
        (field (name "MANUFACTURER") "Yageo")
        (field (name "MANUFACTURER PART NUMBER") "RC0603FR-0710KL")
        (field (name "PACKAGE") "0603")
      )
      (libsource (lib "Resistors") (part "RES; 10K; 0603; SMD; RC0603FR-0710KL"))
    )
    (comp (ref "R_shunt1")
      (value "10mR")
      (footprint "SMD-RES-2512-VD")
      (description "Res Current Sense Metal Plate 2512 0.01 Ohm 1% 3W ±110ppm/°C Molded T/R")
      (fields
        (field (name "MANUFACTURER") "Vishay")
        (field (name "MANUFACTURER PART NUMBER") "WFMA2512R0100FEA")
        (field (name "PACKAGE") "2512")
        (field (name "DESIGNER") "TVBac")
      )
      (libsource (lib "Resistors") (part "RES; SHUNT; 10mOhm; SMD; WFMA2512R0100FEA"))
    )
    (comp (ref "S1")
      (value "1042")
      (footprint "SMD-18650-BAT-1042")
      (description "Battery Holder, SMT, Nylon, High Temp, UL 94V-O, 1 Cell, 18650 ¦ Keystone Electronics 1042")
      (fields (field (name "MANUFACTURER") "Keystone Electronics"))
      (libsource (lib "Socket") (part "1042"))
    )
    (comp (ref "SW1")
      (value "Tactile Switch SPST-NO Top Actuated Surface Mount")
      (footprint "SW-HxLxW-5.0x6.0x3.5-C&K")
      (description "Switch Tactile N.O. SPST Rectangular Button J-Bend 0.05A 12VDC 1.77N SMD T/R")
      (fields
        (field (name "MANUFACTURER") "ITT C&K")
        (field (name "MANUFACTURER PART NUMBER") "PTS636SM50JSMTRLFS")
      )
      (libsource (lib "Button") (part "BUT; SW; SMD; PTS636SM50JSMTRLFS"))
    )
    (comp (ref "SW2")
      (value "Tactile Switch SPST-NO Top Actuated Surface Mount")
      (footprint "SW-HxLxW-5.0x6.0x3.5-C&K")
      (description "Switch Tactile N.O. SPST Rectangular Button J-Bend 0.05A 12VDC 1.77N SMD T/R")
      (fields
        (field (name "MANUFACTURER") "ITT C&K")
        (field (name "MANUFACTURER PART NUMBER") "PTS636SM50JSMTRLFS")
      )
      (libsource (lib "Button") (part "BUT; SW; SMD; PTS636SM50JSMTRLFS"))
    )
  )
  (nets
    (net (code "1") (name "/DS18B20") (class "Default")
      (node (ref "J3") (pin "03") (pinfunction "2_03") (pintype "passive"))
      (node (ref "M1") (pin "19") (pinfunction "IO11_19") (pintype "passive"))
      (node (ref "R15") (pin "1") (pinfunction "1_1") (pintype "passive"))
    )
    (net (code "2") (name "/ESP-D_N") (class "Default")
      (node (ref "J2") (pin "A7") (pinfunction "DN1_A7") (pintype "passive"))
      (node (ref "J2") (pin "B7") (pinfunction "DN2_B7") (pintype "passive"))
      (node (ref "M1") (pin "13") (pinfunction "IO19_13") (pintype "passive"))
    )
    (net (code "3") (name "/ESP-D_P") (class "Default")
      (node (ref "J2") (pin "A6") (pinfunction "DP1_A6") (pintype "passive"))
      (node (ref "J2") (pin "B6") (pinfunction "DP2_B6") (pintype "passive"))
      (node (ref "M1") (pin "14") (pinfunction "IO20_14") (pintype "passive"))
    )
    (net (code "4") (name "/ESP-RX0") (class "Default")
      (node (ref "J1") (pin "02") (pinfunction "2_02") (pintype "passive"))
      (node (ref "M1") (pin "36") (pinfunction "RXD0_36") (pintype "passive"))
    )
    (net (code "5") (name "/ESP-TX0") (class "Default")
      (node (ref "J1") (pin "03") (pinfunction "2_03") (pintype "passive"))
      (node (ref "M1") (pin "37") (pinfunction "TXD0_37") (pintype "passive"))
    )
    (net (code "6") (name "/En_charge") (class "Default")
      (node (ref "M1") (pin "10") (pinfunction "IO17_10") (pintype "passive"))
      (node (ref "R26") (pin "1") (pinfunction "1_1") (pintype "passive"))
    )
    (net (code "7") (name "/LCD-BGR") (class "Default")
      (node (ref "LCD1") (pin "12") (pinfunction "LEDA_12") (pintype "passive"))
      (node (ref "M1") (pin "32") (pinfunction "IO39_32") (pintype "passive"))
    )
    (net (code "8") (name "/LCD-CS") (class "Default")
      (node (ref "LCD1") (pin "7") (pinfunction "CS_7") (pintype "passive"))
      (node (ref "M1") (pin "33") (pinfunction "IO40_33") (pintype "passive"))
    )
    (net (code "9") (name "/LCD-DC") (class "Default")
      (node (ref "LCD1") (pin "5") (pinfunction "D/C_5") (pintype "passive"))
      (node (ref "M1") (pin "35") (pinfunction "IO42_35") (pintype "passive"))
    )
    (net (code "10") (name "/LCD-MOSI") (class "Default")
      (node (ref "LCD1") (pin "3") (pinfunction "SDA_3") (pintype "passive"))
      (node (ref "M1") (pin "39") (pinfunction "IO1_39") (pintype "passive"))
    )
    (net (code "11") (name "/LCD-RST") (class "Default")
      (node (ref "LCD1") (pin "6") (pinfunction "RES_6") (pintype "passive"))
      (node (ref "M1") (pin "34") (pinfunction "IO41_34") (pintype "passive"))
    )
    (net (code "12") (name "/LCD-SCK") (class "Default")
      (node (ref "LCD1") (pin "4") (pinfunction "SCL_4") (pintype "passive"))
      (node (ref "M1") (pin "38") (pinfunction "IO2_38") (pintype "passive"))
    )
    (net (code "13") (name "/LOAD") (class "Default")
      (node (ref "M1") (pin "9") (pinfunction "IO16_9") (pintype "passive"))
      (node (ref "Q3") (pin "1") (pinfunction "G_1") (pintype "passive"))
      (node (ref "R19") (pin "2") (pinfunction "2_2") (pintype "passive"))
    )
    (net (code "14") (name "/SCL") (class "Default")
      (node (ref "IC3") (pin "4") (pinfunction "SCL_4") (pintype "passive"))
      (node (ref "IC5") (pin "2") (pinfunction "SCL_2") (pintype "passive"))
      (node (ref "M1") (pin "11") (pinfunction "IO18_11") (pintype "passive"))
      (node (ref "R18") (pin "2") (pinfunction "2_2") (pintype "passive"))
    )
    (net (code "15") (name "/SDA") (class "Default")
      (node (ref "IC3") (pin "3") (pinfunction "SDA_3") (pintype "passive"))
      (node (ref "IC5") (pin "1") (pinfunction "SDA_1") (pintype "passive"))
      (node (ref "M1") (pin "12") (pinfunction "IO8_12") (pintype "passive"))
      (node (ref "R20") (pin "2") (pinfunction "2_2") (pintype "passive"))
    )
    (net (code "16") (name "3V3") (class "Default")
      (node (ref "C1") (pin "2") (pinfunction "2_2") (pintype "passive"))
      (node (ref "C11") (pin "1") (pinfunction "1_1") (pintype "passive"))
      (node (ref "C15") (pin "1") (pinfunction "1_1") (pintype "passive"))
      (node (ref "C16") (pin "2") (pinfunction "2_2") (pintype "passive"))
      (node (ref "C17") (pin "2") (pinfunction "2_2") (pintype "passive"))
      (node (ref "C2") (pin "1") (pinfunction "1_1") (pintype "passive"))
      (node (ref "C21") (pin "2") (pinfunction "2_2") (pintype "passive"))
      (node (ref "C22") (pin "2") (pinfunction "2_2") (pintype "passive"))
      (node (ref "C23") (pin "2") (pinfunction "2_2") (pintype "passive"))
      (node (ref "C3") (pin "1") (pinfunction "1_1") (pintype "passive"))
      (node (ref "C4") (pin "2") (pinfunction "2_2") (pintype "passive"))
      (node (ref "C5") (pin "2") (pinfunction "2_2") (pintype "passive"))
      (node (ref "C6") (pin "2") (pinfunction "2_2") (pintype "passive"))
      (node (ref "D2") (pin "1") (pinfunction "K_1") (pintype "passive"))
      (node (ref "IC3") (pin "5") (pinfunction "VS_5") (pintype "passive"))
      (node (ref "IC5") (pin "5") (pinfunction "A2_5") (pintype "passive"))
      (node (ref "IC5") (pin "6") (pinfunction "A1_6") (pintype "passive"))
      (node (ref "IC5") (pin "7") (pinfunction "A0_7") (pintype "passive"))
      (node (ref "IC5") (pin "8") (pinfunction "+VS_8") (pintype "passive"))
      (node (ref "J1") (pin "04") (pinfunction "4_04") (pintype "passive"))
      (node (ref "J3") (pin "04") (pinfunction "4_04") (pintype "passive"))
      (node (ref "LCD1") (pin "10") (pinfunction "VCC_10") (pintype "passive"))
      (node (ref "M1") (pin "2") (pinfunction "3V3_2") (pintype "passive"))
      (node (ref "R1") (pin "2") (pinfunction "2_2") (pintype "passive"))
      (node (ref "R15") (pin "2") (pinfunction "2_2") (pintype "passive"))
      (node (ref "R18") (pin "1") (pinfunction "1_1") (pintype "passive"))
      (node (ref "R2") (pin "1") (pinfunction "1_1") (pintype "passive"))
      (node (ref "R20") (pin "1") (pinfunction "1_1") (pintype "passive"))
      (node (ref "R21") (pin "2") (pinfunction "2_2") (pintype "passive"))
      (node (ref "R5") (pin "2") (pinfunction "2_2") (pintype "passive"))
    )
    (net (code "17") (name "BAT+") (class "Default")
      (node (ref "D3") (pin "2") (pinfunction "A_2") (pintype "passive"))
      (node (ref "IC2") (pin "5") (pinfunction "BAT_5") (pintype "passive"))
      (node (ref "J4") (pin "01") (pinfunction "1_01") (pintype "passive"))
      (node (ref "J4") (pin "03") (pinfunction "2_03") (pintype "passive"))
      (node (ref "R16") (pin "1") (pinfunction "1_1") (pintype "passive"))
      (node (ref "R_shunt1") (pin "1") (pinfunction "1_1") (pintype "passive"))
    )
    (net (code "18") (name "GND") (class "Default")
      (node (ref "C1") (pin "1") (pinfunction "1_1") (pintype "passive"))
      (node (ref "C11") (pin "2") (pinfunction "2_2") (pintype "passive"))
      (node (ref "C12") (pin "1") (pinfunction "1_1") (pintype "passive"))
      (node (ref "C13") (pin "1") (pinfunction "1_1") (pintype "passive"))
      (node (ref "C14") (pin "1") (pinfunction "1_1") (pintype "passive"))
      (node (ref "C15") (pin "2") (pinfunction "2_2") (pintype "passive"))
      (node (ref "C16") (pin "1") (pinfunction "1_1") (pintype "passive"))
      (node (ref "C17") (pin "1") (pinfunction "1_1") (pintype "passive"))
      (node (ref "C2") (pin "2") (pinfunction "2_2") (pintype "passive"))
      (node (ref "C21") (pin "1") (pinfunction "1_1") (pintype "passive"))
      (node (ref "C22") (pin "1") (pinfunction "1_1") (pintype "passive"))
      (node (ref "C23") (pin "1") (pinfunction "1_1") (pintype "passive"))
      (node (ref "C3") (pin "2") (pinfunction "2_2") (pintype "passive"))
      (node (ref "C4") (pin "1") (pinfunction "1_1") (pintype "passive"))
      (node (ref "C5") (pin "1") (pinfunction "1_1") (pintype "passive"))
      (node (ref "C6") (pin "1") (pinfunction "1_1") (pintype "passive"))
      (node (ref "C7") (pin "1") (pinfunction "1_1") (pintype "passive"))
      (node (ref "C8") (pin "1") (pinfunction "1_1") (pintype "passive"))
      (node (ref "IC1") (pin "2") (pinfunction "GND_2") (pintype "passive"))
      (node (ref "IC2") (pin "3") (pinfunction "GND_3") (pintype "passive"))
      (node (ref "IC2") (pin "9") (pinfunction "EP_9") (pintype "passive"))
      (node (ref "IC3") (pin "1") (pinfunction "A1_1") (pintype "passive"))
      (node (ref "IC3") (pin "2") (pinfunction "A0_2") (pintype "passive"))
      (node (ref "IC3") (pin "6") (pinfunction "GND_6") (pintype "passive"))
      (node (ref "IC4") (pin "1") (pinfunction "VM_1") (pintype "passive"))
      (node (ref "IC4") (pin "2") (pinfunction "VM_2") (pintype "passive"))
      (node (ref "IC4") (pin "3") (pinfunction "VM_3") (pintype "passive"))
      (node (ref "IC4") (pin "4") (pinfunction "VM_4") (pintype "passive"))
      (node (ref "IC5") (pin "4") (pinfunction "GND_4") (pintype "passive"))
      (node (ref "J1") (pin "01") (pinfunction "1_01") (pintype "passive"))
      (node (ref "J2") (pin "A1B12") (pinfunction "GND1_A1B12") (pintype "passive"))
      (node (ref "J2") (pin "B1A12") (pinfunction "GND2_B1A12") (pintype "passive"))
      (node (ref "J2") (pin "SHIELD") (pinfunction "SHIELD_SHIELD") (pintype "passive"))
      (node (ref "J3") (pin "01") (pinfunction "1_01") (pintype "passive"))
      (node (ref "L2") (pin "2") (pinfunction "2_2") (pintype "passive"))
      (node (ref "LCD1") (pin "1") (pinfunction "TP0_1") (pintype "passive"))
      (node (ref "LCD1") (pin "13") (pinfunction "GND_13") (pintype "passive"))
      (node (ref "LCD1") (pin "14") (pinfunction "GND_14") (pintype "passive"))
      (node (ref "LCD1") (pin "15") (pinfunction "GND_15") (pintype "passive"))
      (node (ref "LCD1") (pin "16") (pinfunction "GND_16") (pintype "passive"))
      (node (ref "LCD1") (pin "17") (pinfunction "GND_17") (pintype "passive"))
      (node (ref "LCD1") (pin "2") (pinfunction "TP1_2") (pintype "passive"))
      (node (ref "LCD1") (pin "8") (pinfunction "GND_8") (pintype "passive"))
      (node (ref "M1") (pin "1") (pinfunction "GND_1") (pintype "passive"))
      (node (ref "M1") (pin "40") (pinfunction "GND_40") (pintype "passive"))
      (node (ref "M1") (pin "41") (pinfunction "GND_41") (pintype "passive"))
      (node (ref "M1") (pin "42") (pinfunction "GND_42") (pintype "passive"))
      (node (ref "M1") (pin "43") (pinfunction "GND_43") (pintype "passive"))
      (node (ref "M1") (pin "44") (pinfunction "GND_44") (pintype "passive"))
      (node (ref "M1") (pin "45") (pinfunction "GND_45") (pintype "passive"))
      (node (ref "M1") (pin "46") (pinfunction "GND_46") (pintype "passive"))
      (node (ref "M1") (pin "47") (pinfunction "GND_47") (pintype "passive"))
      (node (ref "M1") (pin "48") (pinfunction "GND_48") (pintype "passive"))
      (node (ref "M1") (pin "49") (pinfunction "GND_49") (pintype "passive"))
      (node (ref "Q1") (pin "2") (pinfunction "S_2") (pintype "passive"))
      (node (ref "Q3") (pin "2") (pinfunction "S_2") (pintype "passive"))
      (node (ref "R11") (pin "2") (pinfunction "2_2") (pintype "passive"))
      (node (ref "R12") (pin "1") (pinfunction "1_1") (pintype "passive"))
      (node (ref "R13") (pin "2") (pinfunction "2_2") (pintype "passive"))
      (node (ref "R14") (pin "2") (pinfunction "2_2") (pintype "passive"))
      (node (ref "R19") (pin "1") (pinfunction "1_1") (pintype "passive"))
      (node (ref "R24") (pin "2") (pinfunction "2_2") (pintype "passive"))
      (node (ref "R28") (pin "1") (pinfunction "1_1") (pintype "passive"))
      (node (ref "R4") (pin "2") (pinfunction "2_2") (pintype "passive"))
      (node (ref "R9") (pin "2") (pinfunction "2_2") (pintype "passive"))
      (node (ref "SW1") (pin "1") (pinfunction "COM_1") (pintype "passive"))
      (node (ref "SW2") (pin "1") (pinfunction "COM_1") (pintype "passive"))
    )
    (net (code "19") (name "Net-(D2-A)") (class "Default")
      (node (ref "C9") (pin "2") (pinfunction "2_2") (pintype "passive"))
      (node (ref "D2") (pin "2") (pinfunction "A_2") (pintype "passive"))
      (node (ref "L2") (pin "1") (pinfunction "1_1") (pintype "passive"))
    )
    (net (code "20") (name "Net-(D4-Pad2)") (class "Default")
      (node (ref "D4") (pin "2") (pinfunction "2_2") (pintype "passive"))
      (node (ref "R6") (pin "1") (pinfunction "1_1") (pintype "passive"))
    )
    (net (code "21") (name "Net-(D5-Pad2)") (class "Default")
      (node (ref "D5") (pin "2") (pinfunction "2_2") (pintype "passive"))
      (node (ref "R7") (pin "1") (pinfunction "1_1") (pintype "passive"))
    )
    (net (code "22") (name "Net-(IC1-FB)") (class "Default")
      (node (ref "IC1") (pin "3") (pinfunction "FB_3") (pintype "passive"))
      (node (ref "R12") (pin "2") (pinfunction "2_2") (pintype "passive"))
      (node (ref "R5") (pin "1") (pinfunction "1_1") (pintype "passive"))
    )
    (net (code "23") (name "Net-(IC1-SW)") (class "Default")
      (node (ref "C9") (pin "1") (pinfunction "1_1") (pintype "passive"))
      (node (ref "IC1") (pin "1") (pinfunction "SW_1") (pintype "passive"))
      (node (ref "L1") (pin "2") (pinfunction "2_2") (pintype "passive"))
    )
    (net (code "24") (name "Net-(IC2-CE)") (class "Default")
      (node (ref "IC2") (pin "8") (pinfunction "CE_8") (pintype "passive"))
      (node (ref "Q1") (pin "3") (pinfunction "D_3") (pintype "passive"))
      (node (ref "R10") (pin "1") (pinfunction "1_1") (pintype "passive"))
    )
    (net (code "25") (name "Net-(IC2-PROG)") (class "Default")
      (node (ref "IC2") (pin "2") (pinfunction "PROG_2") (pintype "passive"))
      (node (ref "R14") (pin "1") (pinfunction "1_1") (pintype "passive"))
    )
    (net (code "26") (name "Net-(IC2-TEMP)") (class "Default")
      (node (ref "IC2") (pin "1") (pinfunction "TEMP_1") (pintype "passive"))
      (node (ref "R11") (pin "1") (pinfunction "1_1") (pintype "passive"))
      (node (ref "R8") (pin "2") (pinfunction "2_2") (pintype "passive"))
      (node (ref "R9") (pin "1") (pinfunction "1_1") (pintype "passive"))
    )
    (net (code "27") (name "Net-(IC2-VCC)") (class "Default")
      (node (ref "D4") (pin "1") (pinfunction "1_1") (pintype "passive"))
      (node (ref "D5") (pin "1") (pinfunction "1_1") (pintype "passive"))
      (node (ref "IC2") (pin "4") (pinfunction "VCC_4") (pintype "passive"))
      (node (ref "R10") (pin "2") (pinfunction "2_2") (pintype "passive"))
      (node (ref "R3") (pin "2") (pinfunction "2_2") (pintype "passive"))
      (node (ref "R8") (pin "1") (pinfunction "1_1") (pintype "passive"))
    )
    (net (code "28") (name "Net-(IC2-~{CHRG})") (class "Default")
      (node (ref "IC2") (pin "7") (pinfunction "~{CHRG}_7") (pintype "passive"))
      (node (ref "R6") (pin "2") (pinfunction "2_2") (pintype "passive"))
    )
    (net (code "29") (name "Net-(IC2-~{STDBY})") (class "Default")
      (node (ref "IC2") (pin "6") (pinfunction "~{STDBY}_6") (pintype "passive"))
      (node (ref "R7") (pin "2") (pinfunction "2_2") (pintype "passive"))
    )
    (net (code "30") (name "Net-(IC3-VIN+)") (class "Default")
      (node (ref "C19") (pin "1") (pinfunction "1_1") (pintype "passive"))
      (node (ref "IC3") (pin "8") (pinfunction "VIN+_8") (pintype "passive"))
      (node (ref "R16") (pin "2") (pinfunction "2_2") (pintype "passive"))
    )
    (net (code "31") (name "Net-(IC3-VIN-)") (class "Default")
      (node (ref "C19") (pin "2") (pinfunction "2_2") (pintype "passive"))
      (node (ref "IC3") (pin "7") (pinfunction "VIN-_7") (pintype "passive"))
      (node (ref "R17") (pin "2") (pinfunction "2_2") (pintype "passive"))
    )
    (net (code "32") (name "Net-(IC4-EPAD)") (class "Default")
      (node (ref "C20") (pin "1") (pinfunction "1_1") (pintype "passive"))
      (node (ref "IC4") (pin "5") (pinfunction "GND_5") (pintype "passive"))
      (node (ref "IC4") (pin "7") (pinfunction "GND_7") (pintype "passive"))
      (node (ref "IC4") (pin "8") (pinfunction "GND_8") (pintype "passive"))
      (node (ref "IC4") (pin "9") (pinfunction "EPAD_9") (pintype "passive"))
      (node (ref "S1") (pin "N") (pinfunction "NEG_N") (pintype "passive"))
    )
    (net (code "33") (name "Net-(IC4-VDD)") (class "Default")
      (node (ref "C20") (pin "2") (pinfunction "2_2") (pintype "passive"))
      (node (ref "IC4") (pin "6") (pinfunction "VDD_6") (pintype "passive"))
      (node (ref "R25") (pin "1") (pinfunction "1_1") (pintype "passive"))
    )
    (net (code "34") (name "Net-(IC5-OS)") (class "Default")
      (node (ref "IC5") (pin "3") (pinfunction "OS_3") (pintype "passive"))
      (node (ref "R21") (pin "1") (pinfunction "1_1") (pintype "passive"))
    )
    (net (code "35") (name "Net-(J2-CC1)") (class "Default")
      (node (ref "J2") (pin "A5") (pinfunction "CC1_A5") (pintype "passive"))
      (node (ref "R13") (pin "1") (pinfunction "1_1") (pintype "passive"))
    )
    (net (code "36") (name "Net-(J2-CC2)") (class "Default")
      (node (ref "J2") (pin "B5") (pinfunction "CC2_B5") (pintype "passive"))
      (node (ref "R4") (pin "1") (pinfunction "1_1") (pintype "passive"))
    )
    (net (code "37") (name "Net-(J4-4)") (class "Default")
      (node (ref "J4") (pin "02") (pinfunction "2_02") (pintype "passive"))
      (node (ref "J4") (pin "04") (pinfunction "4_04") (pintype "passive"))
      (node (ref "Q3") (pin "3") (pinfunction "D_3") (pintype "passive"))
    )
    (net (code "38") (name "Net-(LCD1-LEDK)") (class "Default")
      (node (ref "LCD1") (pin "11") (pinfunction "LEDK_11") (pintype "passive"))
      (node (ref "R24") (pin "1") (pinfunction "1_1") (pintype "passive"))
    )
    (net (code "39") (name "Net-(M1-EN)") (class "Default")
      (node (ref "C7") (pin "2") (pinfunction "2_2") (pintype "passive"))
      (node (ref "M1") (pin "3") (pinfunction "EN_3") (pintype "passive"))
      (node (ref "R1") (pin "1") (pinfunction "1_1") (pintype "passive"))
      (node (ref "SW1") (pin "2") (pinfunction "NO_2") (pintype "passive"))
    )
    (net (code "40") (name "Net-(M1-IO0)") (class "Default")
      (node (ref "C8") (pin "2") (pinfunction "2_2") (pintype "passive"))
      (node (ref "M1") (pin "27") (pinfunction "IO0_27") (pintype "passive"))
      (node (ref "R2") (pin "2") (pinfunction "2_2") (pintype "passive"))
      (node (ref "SW2") (pin "2") (pinfunction "NO_2") (pintype "passive"))
    )
    (net (code "41") (name "Net-(Q1-G)") (class "Default")
      (node (ref "Q1") (pin "1") (pinfunction "G_1") (pintype "passive"))
      (node (ref "R26") (pin "2") (pinfunction "2_2") (pintype "passive"))
      (node (ref "R28") (pin "2") (pinfunction "2_2") (pintype "passive"))
    )
    (net (code "42") (name "Net-(S1-POS)") (class "Default")
      (node (ref "R17") (pin "1") (pinfunction "1_1") (pintype "passive"))
      (node (ref "R25") (pin "2") (pinfunction "2_2") (pintype "passive"))
      (node (ref "R_shunt1") (pin "2") (pinfunction "2_2") (pintype "passive"))
      (node (ref "S1") (pin "P") (pinfunction "POS_P") (pintype "passive"))
    )
    (net (code "43") (name "VBUS") (class "Default")
      (node (ref "D1") (pin "2") (pinfunction "A_2") (pintype "passive"))
      (node (ref "J2") (pin "A4B9") (pinfunction "VBUS1_A4B9") (pintype "passive"))
      (node (ref "J2") (pin "B4A9") (pinfunction "VBUS2_B4A9") (pintype "passive"))
      (node (ref "R3") (pin "1") (pinfunction "1_1") (pintype "passive"))
    )
    (net (code "44") (name "VIN") (class "Default")
      (node (ref "C12") (pin "2") (pinfunction "2_2") (pintype "passive"))
      (node (ref "C13") (pin "2") (pinfunction "2_2") (pintype "passive"))
      (node (ref "C14") (pin "2") (pinfunction "2_2") (pintype "passive"))
      (node (ref "D1") (pin "1") (pinfunction "K_1") (pintype "passive"))
      (node (ref "D3") (pin "1") (pinfunction "K_1") (pintype "passive"))
      (node (ref "IC1") (pin "4") (pinfunction "EN_4") (pintype "passive"))
      (node (ref "IC1") (pin "5") (pinfunction "VIN_5") (pintype "passive"))
      (node (ref "L1") (pin "1") (pinfunction "1_1") (pintype "passive"))
    )
    (net (code "45") (name "unconnected-(IC1-NC-Pad6)") (class "Default")
      (node (ref "IC1") (pin "6") (pinfunction "NC_6") (pintype "passive"))
    )
    (net (code "46") (name "unconnected-(J2-SBU1-PadA8)") (class "Default")
      (node (ref "J2") (pin "A8") (pinfunction "SBU1_A8") (pintype "passive+no_connect"))
    )
    (net (code "47") (name "unconnected-(J2-SBU2-PadB8)") (class "Default")
      (node (ref "J2") (pin "B8") (pinfunction "SBU2_B8") (pintype "passive+no_connect"))
    )
    (net (code "48") (name "unconnected-(J3-2-Pad02)") (class "Default")
      (node (ref "J3") (pin "02") (pinfunction "2_02") (pintype "passive+no_connect"))
    )
    (net (code "49") (name "unconnected-(LCD1-NC-Pad9)") (class "Default")
      (node (ref "LCD1") (pin "9") (pinfunction "NC_9") (pintype "passive+no_connect"))
    )
    (net (code "50") (name "unconnected-(M1-IO3-Pad15)") (class "Default")
      (node (ref "M1") (pin "15") (pinfunction "IO3_15") (pintype "passive+no_connect"))
    )
    (net (code "51") (name "unconnected-(M1-IO4-Pad4)") (class "Default")
      (node (ref "M1") (pin "4") (pinfunction "IO4_4") (pintype "passive"))
    )
    (net (code "52") (name "unconnected-(M1-IO5-Pad5)") (class "Default")
      (node (ref "M1") (pin "5") (pinfunction "IO5_5") (pintype "passive"))
    )
    (net (code "53") (name "unconnected-(M1-IO6-Pad6)") (class "Default")
      (node (ref "M1") (pin "6") (pinfunction "IO6_6") (pintype "passive"))
    )
    (net (code "54") (name "unconnected-(M1-IO7-Pad7)") (class "Default")
      (node (ref "M1") (pin "7") (pinfunction "IO7_7") (pintype "passive"))
    )
    (net (code "55") (name "unconnected-(M1-IO9-Pad17)") (class "Default")
      (node (ref "M1") (pin "17") (pinfunction "IO9_17") (pintype "passive"))
    )
    (net (code "56") (name "unconnected-(M1-IO10-Pad18)") (class "Default")
      (node (ref "M1") (pin "18") (pinfunction "IO10_18") (pintype "passive"))
    )
    (net (code "57") (name "unconnected-(M1-IO12-Pad20)") (class "Default")
      (node (ref "M1") (pin "20") (pinfunction "IO12_20") (pintype "passive"))
    )
    (net (code "58") (name "unconnected-(M1-IO13-Pad21)") (class "Default")
      (node (ref "M1") (pin "21") (pinfunction "IO13_21") (pintype "passive"))
    )
    (net (code "59") (name "unconnected-(M1-IO14-Pad22)") (class "Default")
      (node (ref "M1") (pin "22") (pinfunction "IO14_22") (pintype "passive"))
    )
    (net (code "60") (name "unconnected-(M1-IO15-Pad8)") (class "Default")
      (node (ref "M1") (pin "8") (pinfunction "IO15_8") (pintype "passive"))
    )
    (net (code "61") (name "unconnected-(M1-IO21-Pad23)") (class "Default")
      (node (ref "M1") (pin "23") (pinfunction "IO21_23") (pintype "passive"))
    )
    (net (code "62") (name "unconnected-(M1-IO35-Pad28)") (class "Default")
      (node (ref "M1") (pin "28") (pinfunction "IO35_28") (pintype "passive+no_connect"))
    )
    (net (code "63") (name "unconnected-(M1-IO36-Pad29)") (class "Default")
      (node (ref "M1") (pin "29") (pinfunction "IO36_29") (pintype "passive+no_connect"))
    )
    (net (code "64") (name "unconnected-(M1-IO37-Pad30)") (class "Default")
      (node (ref "M1") (pin "30") (pinfunction "IO37_30") (pintype "passive+no_connect"))
    )
    (net (code "65") (name "unconnected-(M1-IO38-Pad31)") (class "Default")
      (node (ref "M1") (pin "31") (pinfunction "IO38_31") (pintype "passive"))
    )
    (net (code "66") (name "unconnected-(M1-IO45-Pad26)") (class "Default")
      (node (ref "M1") (pin "26") (pinfunction "IO45_26") (pintype "passive+no_connect"))
    )
    (net (code "67") (name "unconnected-(M1-IO46-Pad16)") (class "Default")
      (node (ref "M1") (pin "16") (pinfunction "IO46_16") (pintype "passive+no_connect"))
    )
    (net (code "68") (name "unconnected-(M1-IO47-Pad24)") (class "Default")
      (node (ref "M1") (pin "24") (pinfunction "IO47_24") (pintype "passive"))
    )
    (net (code "69") (name "unconnected-(M1-IO48-Pad25)") (class "Default")
      (node (ref "M1") (pin "25") (pinfunction "IO48_25") (pintype "passive"))
    )
  )
)
